# OMODRI_Encoders.net
KiCad netlist of a schematic drawn in Altium Designer
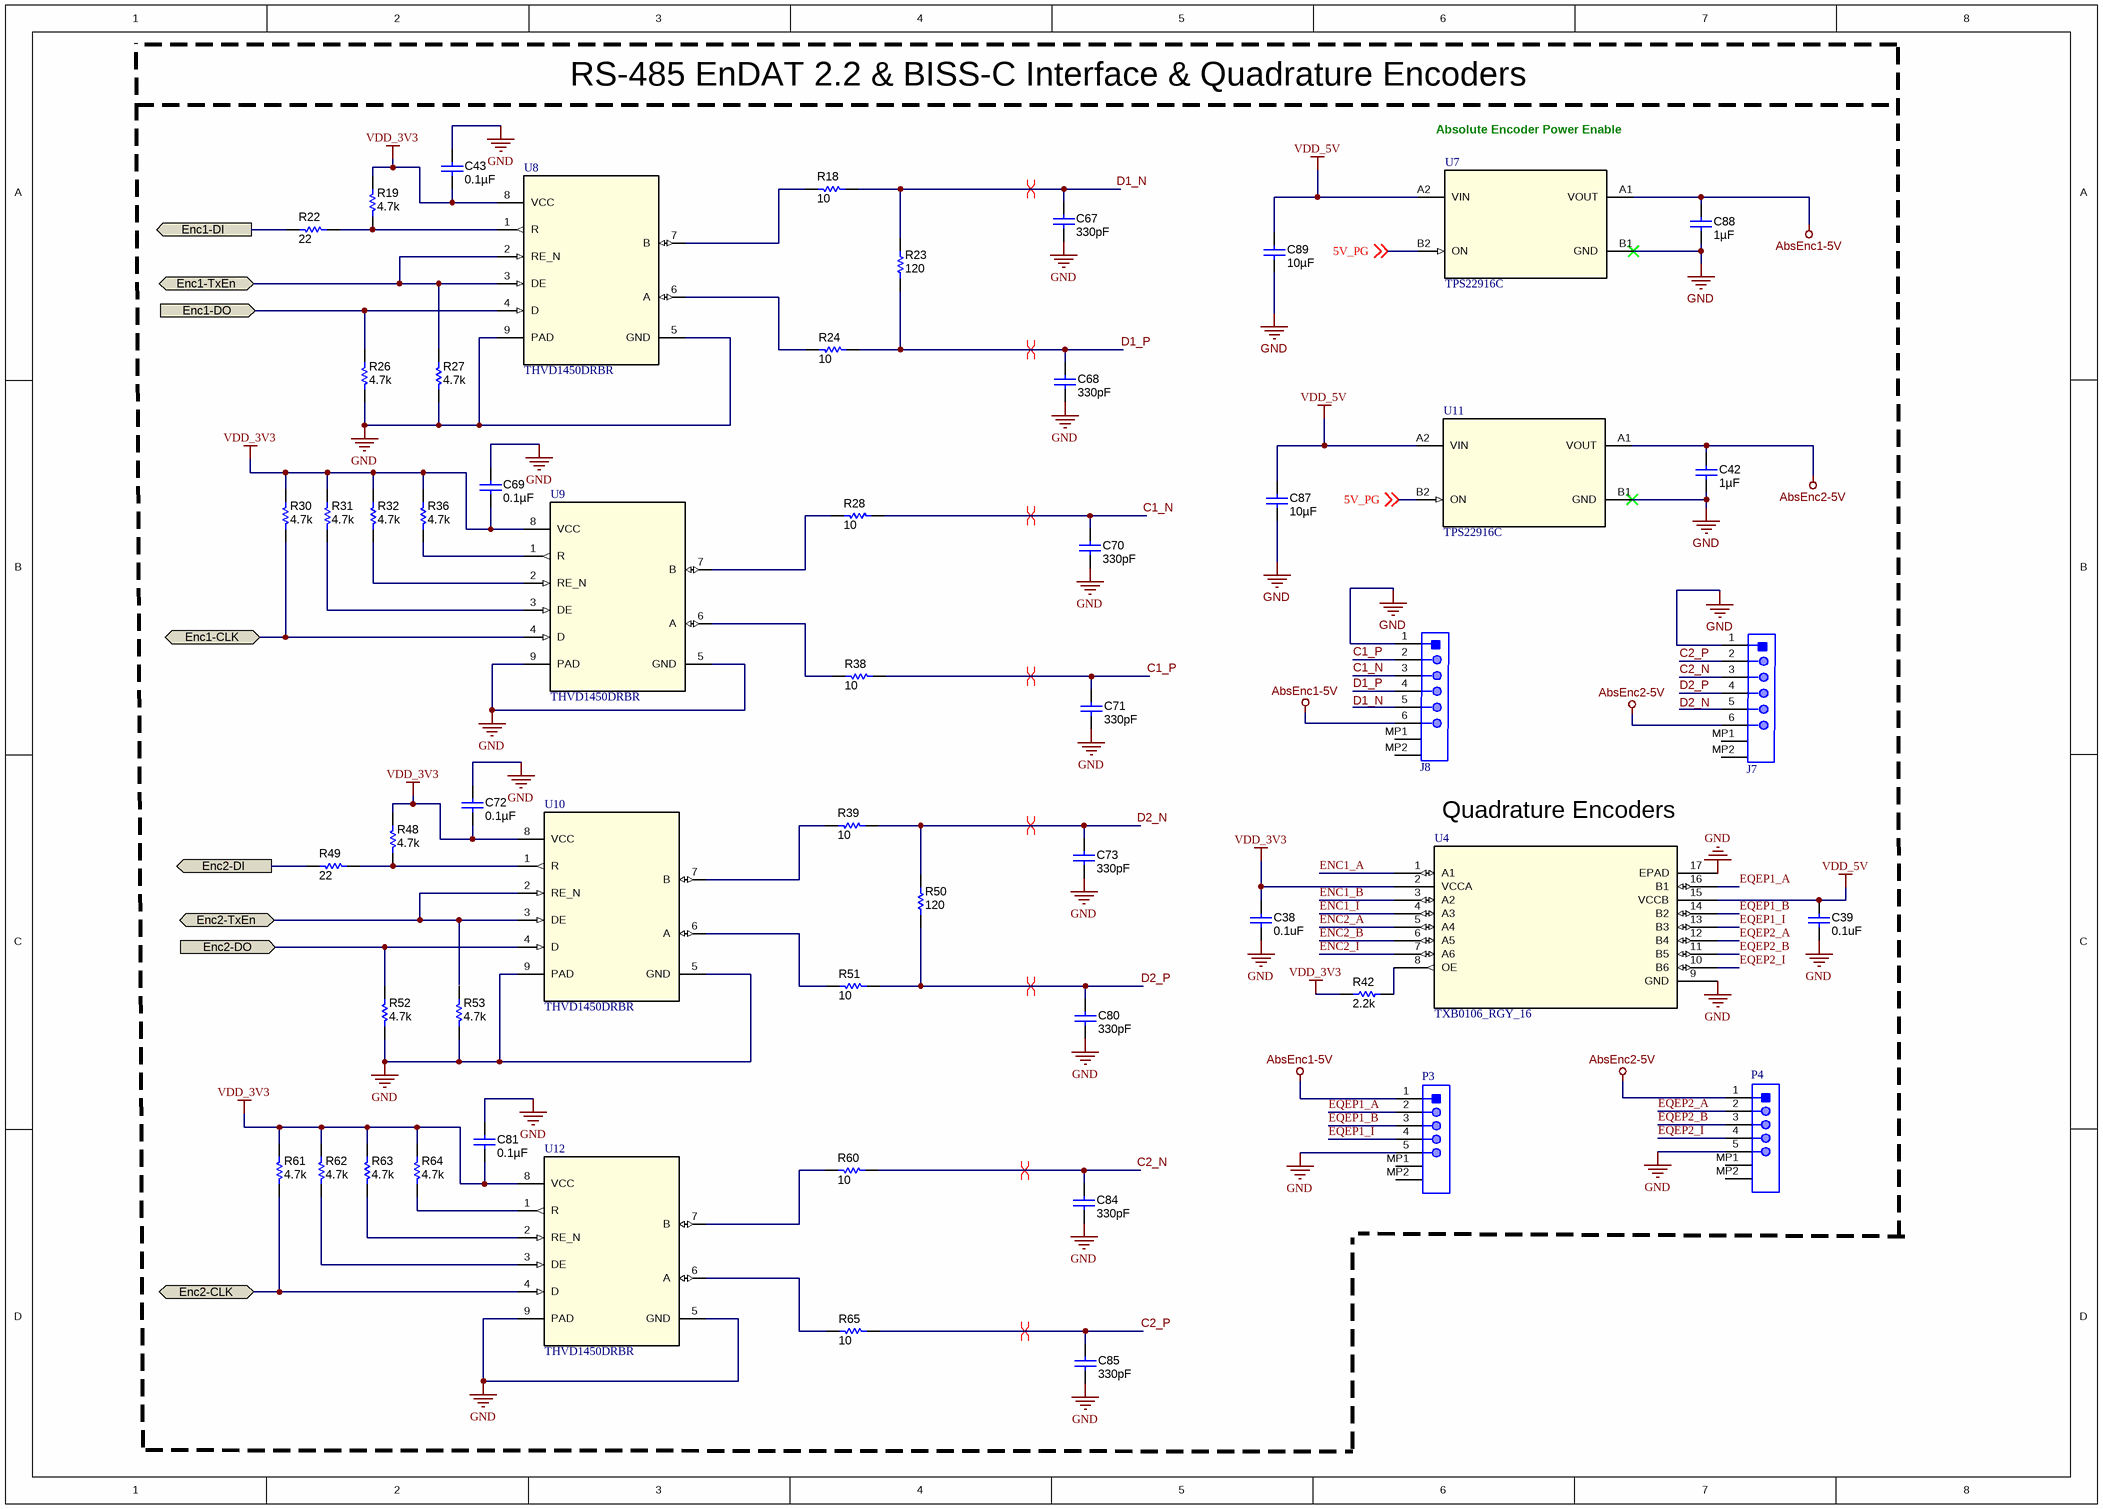
[diagram p0: OMODRI_Encoders.SchDoc]

(export (version "E")
  (design (tool "Eeschema 10.0.6"))
  (components
    (comp (ref "C38")
      (value "CL05B104KP5NNNC")
      (footprint "0402")
      (description "CAP, CERM, 0.1 uF, 10 V, +/- 10%, X7R, 0402")
      (fields
        (field (name "VALUEDISPLAYED") "0.1uF")
        (field (name "MANUFACTURER") "Samsung Electro-Mechanics")
        (field (name "PUBLISHER") "Texas Instruments")
      )
      (libsource (lib "Altium Vault - TI") (part "Capacitor"))
    )
    (comp (ref "C39")
      (value "CL05B104KP5NNNC")
      (footprint "0402")
      (description "CAP, CERM, 0.1 uF, 10 V, +/- 10%, X7R, 0402")
      (fields
        (field (name "VALUEDISPLAYED") "0.1uF")
        (field (name "MANUFACTURER") "Samsung Electro-Mechanics")
        (field (name "PUBLISHER") "Texas Instruments")
      )
      (libsource (lib "Altium Vault - TI") (part "Capacitor"))
    )
    (comp (ref "C42")
      (value "TMK212BJ105KG-T")
      (footprint "0805_HV")
      (description "CAP, CERM, 1 µF, 20 V, +/- 10%, X5R, 0805")
      (fields
        (field (name "VALUEDISPLAYED") "1µF")
        (field (name "MANUFACTURER") "Taiyo Yuden")
        (field (name "PUBLISHER") "Texas Instruments")
      )
      (libsource (lib "Capacitor_Ceramic") (part "TMK212BJ105KG-T"))
    )
    (comp (ref "C43")
      (value "06033D104KAT2A")
      (footprint "0603")
      (description "CAP, CERM, 0.1uF, 25V, +/-10%, X5R, 0603")
      (fields
        (field (name "VALUEDISPLAYED") "0.1µF")
        (field (name "MANUFACTURER") "AVX")
        (field (name "PUBLISHER") "Texas Instruments")
      )
      (libsource (lib "Capacitor_Ceramic") (part "06033D104KAT2A"))
    )
    (comp (ref "C67")
      (value "GRM188R71H331KA01D")
      (footprint "0603")
      (description "CAP, CERM, 330pF, 50V, +/-10%, X7R, 0603")
      (fields
        (field (name "VALUEDISPLAYED") "330pF")
        (field (name "MANUFACTURER") "MuRata")
        (field (name "PUBLISHER") "Texas Instruments")
      )
      (libsource (lib "Capacitor_Ceramic") (part "GRM188R71H331KA01D"))
    )
    (comp (ref "C68")
      (value "GRM188R71H331KA01D")
      (footprint "0603")
      (description "CAP, CERM, 330pF, 50V, +/-10%, X7R, 0603")
      (fields
        (field (name "VALUEDISPLAYED") "330pF")
        (field (name "MANUFACTURER") "MuRata")
        (field (name "PUBLISHER") "Texas Instruments")
      )
      (libsource (lib "Capacitor_Ceramic") (part "GRM188R71H331KA01D"))
    )
    (comp (ref "C69")
      (value "06033D104KAT2A")
      (footprint "0603")
      (description "CAP, CERM, 0.1uF, 25V, +/-10%, X5R, 0603")
      (fields
        (field (name "VALUEDISPLAYED") "0.1µF")
        (field (name "MANUFACTURER") "AVX")
        (field (name "PUBLISHER") "Texas Instruments")
      )
      (libsource (lib "Capacitor_Ceramic") (part "06033D104KAT2A"))
    )
    (comp (ref "C70")
      (value "GRM188R71H331KA01D")
      (footprint "0603")
      (description "CAP, CERM, 330pF, 50V, +/-10%, X7R, 0603")
      (fields
        (field (name "VALUEDISPLAYED") "330pF")
        (field (name "MANUFACTURER") "MuRata")
        (field (name "PUBLISHER") "Texas Instruments")
      )
      (libsource (lib "Capacitor_Ceramic") (part "GRM188R71H331KA01D"))
    )
    (comp (ref "C71")
      (value "GRM188R71H331KA01D")
      (footprint "0603")
      (description "CAP, CERM, 330pF, 50V, +/-10%, X7R, 0603")
      (fields
        (field (name "VALUEDISPLAYED") "330pF")
        (field (name "MANUFACTURER") "MuRata")
        (field (name "PUBLISHER") "Texas Instruments")
      )
      (libsource (lib "Capacitor_Ceramic") (part "GRM188R71H331KA01D"))
    )
    (comp (ref "C72")
      (value "06033D104KAT2A")
      (footprint "0603")
      (description "CAP, CERM, 0.1uF, 25V, +/-10%, X5R, 0603")
      (fields
        (field (name "VALUEDISPLAYED") "0.1µF")
        (field (name "MANUFACTURER") "AVX")
        (field (name "PUBLISHER") "Texas Instruments")
      )
      (libsource (lib "Capacitor_Ceramic") (part "06033D104KAT2A"))
    )
    (comp (ref "C73")
      (value "GRM188R71H331KA01D")
      (footprint "0603")
      (description "CAP, CERM, 330pF, 50V, +/-10%, X7R, 0603")
      (fields
        (field (name "VALUEDISPLAYED") "330pF")
        (field (name "MANUFACTURER") "MuRata")
        (field (name "PUBLISHER") "Texas Instruments")
      )
      (libsource (lib "Capacitor_Ceramic") (part "GRM188R71H331KA01D"))
    )
    (comp (ref "C80")
      (value "GRM188R71H331KA01D")
      (footprint "0603")
      (description "CAP, CERM, 330pF, 50V, +/-10%, X7R, 0603")
      (fields
        (field (name "VALUEDISPLAYED") "330pF")
        (field (name "MANUFACTURER") "MuRata")
        (field (name "PUBLISHER") "Texas Instruments")
      )
      (libsource (lib "Capacitor_Ceramic") (part "GRM188R71H331KA01D"))
    )
    (comp (ref "C81")
      (value "06033D104KAT2A")
      (footprint "0603")
      (description "CAP, CERM, 0.1uF, 25V, +/-10%, X5R, 0603")
      (fields
        (field (name "VALUEDISPLAYED") "0.1µF")
        (field (name "MANUFACTURER") "AVX")
        (field (name "PUBLISHER") "Texas Instruments")
      )
      (libsource (lib "Capacitor_Ceramic") (part "06033D104KAT2A"))
    )
    (comp (ref "C84")
      (value "GRM188R71H331KA01D")
      (footprint "0603")
      (description "CAP, CERM, 330pF, 50V, +/-10%, X7R, 0603")
      (fields
        (field (name "VALUEDISPLAYED") "330pF")
        (field (name "MANUFACTURER") "MuRata")
        (field (name "PUBLISHER") "Texas Instruments")
      )
      (libsource (lib "Capacitor_Ceramic") (part "GRM188R71H331KA01D"))
    )
    (comp (ref "C85")
      (value "GRM188R71H331KA01D")
      (footprint "0603")
      (description "CAP, CERM, 330pF, 50V, +/-10%, X7R, 0603")
      (fields
        (field (name "VALUEDISPLAYED") "330pF")
        (field (name "MANUFACTURER") "MuRata")
        (field (name "PUBLISHER") "Texas Instruments")
      )
      (libsource (lib "Capacitor_Ceramic") (part "GRM188R71H331KA01D"))
    )
    (comp (ref "C87")
      (value "GRM21BR61E106KA73L")
      (footprint "0805_HV")
      (description "CAP, CERM, 10 µF, 25 V,+/- 10%, X5R, 0805")
      (fields
        (field (name "VALUEDISPLAYED") "10µF")
        (field (name "MANUFACTURER") "MuRata")
        (field (name "PUBLISHER") "Texas Instruments")
      )
      (libsource (lib "Capacitor_Ceramic") (part "GRM21BR61E106KA73L"))
    )
    (comp (ref "C88")
      (value "TMK212BJ105KG-T")
      (footprint "0805_HV")
      (description "CAP, CERM, 1 µF, 20 V, +/- 10%, X5R, 0805")
      (fields
        (field (name "VALUEDISPLAYED") "1µF")
        (field (name "MANUFACTURER") "Taiyo Yuden")
        (field (name "PUBLISHER") "Texas Instruments")
      )
      (libsource (lib "Capacitor_Ceramic") (part "TMK212BJ105KG-T"))
    )
    (comp (ref "C89")
      (value "GRM21BR61E106KA73L")
      (footprint "0805_HV")
      (description "CAP, CERM, 10 µF, 25 V,+/- 10%, X5R, 0805")
      (fields
        (field (name "VALUEDISPLAYED") "10µF")
        (field (name "MANUFACTURER") "MuRata")
        (field (name "PUBLISHER") "Texas Instruments")
      )
      (libsource (lib "Capacitor_Ceramic") (part "GRM21BR61E106KA73L"))
    )
    (comp (ref "J7")
      (value "Conn_JST_BM06B-GHS-TBT_LF_SN_N_eec")
      (footprint "JST_BM06B-GHS-TBT_LF_SN_N_0")
      (description "CONN HEADER GH TOP 6POS 1.25MM")
      (fields (field (name "MANUFACTURER") "JST") (field (name "DIGIKEY PART NUMBER") "455-1582-1-ND"))
      (libsource (lib "JST_GH") (part "Conn_JST_BM06B-GHS-TBT_LF_SN_N_eec"))
    )
    (comp (ref "J8")
      (value "Conn_JST_BM06B-GHS-TBT_LF_SN_N_eec")
      (footprint "JST_BM06B-GHS-TBT_LF_SN_N_0")
      (description "CONN HEADER GH TOP 6POS 1.25MM")
      (fields (field (name "MANUFACTURER") "JST") (field (name "DIGIKEY PART NUMBER") "455-1582-1-ND"))
      (libsource (lib "JST_GH") (part "Conn_JST_BM06B-GHS-TBT_LF_SN_N_eec"))
    )
    (comp (ref "P3")
      (value "BM05B-GHS-TBT(LF)(SN)")
      (footprint "JST-BM05B-GHS-TBT_V")
      (fields (field (name "MANUFACTURER") "JST"))
      (libsource (lib "JST_GH") (part "CMP-2000-05958-1"))
    )
    (comp (ref "P4")
      (value "BM05B-GHS-TBT(LF)(SN)")
      (footprint "JST-BM05B-GHS-TBT_V")
      (fields (field (name "MANUFACTURER") "JST"))
      (libsource (lib "JST_GH") (part "CMP-2000-05958-1"))
    )
    (comp (ref "R18")
      (value "10")
      (footprint "0603")
      (description "RES, 10 ohm, 5%, 0.25W, 0603")
      (fields
        (field (name "PARTNUMBER") "CRCW060310R0JNEAHP")
        (field (name "MANUFACTURER") "Vishay-Dale")
        (field (name "PUBLISHER") "Texas Instruments")
      )
      (libsource (lib "Resistor_0603") (part "CRCW060310R0JNEAHP"))
    )
    (comp (ref "R19")
      (value "4.7k")
      (footprint "0603")
      (description "RES, 4.7k ohm, 5%, 0.1W, 0603")
      (fields
        (field (name "PARTNUMBER") "CRCW06034K70JNEA")
        (field (name "MANUFACTURER") "Vishay-Dale")
        (field (name "PUBLISHER") "Texas Instruments")
      )
      (libsource (lib "Resistor_0603") (part "CRCW06034K70JNEA"))
    )
    (comp (ref "R22")
      (value "22")
      (footprint "0603")
      (description "RES, 22 ohm, 5%, 0.1W, 0603")
      (fields
        (field (name "PARTNUMBER") "CRCW060322R0JNEA")
        (field (name "MANUFACTURER") "Vishay-Dale")
        (field (name "PUBLISHER") "Texas Instruments")
      )
      (libsource (lib "Resistor_0603") (part "CRCW060322R0JNEA"))
    )
    (comp (ref "R23")
      (value "CRCW0603120RJNEA")
      (footprint "0603")
      (description "RES, 120, 5%, 0.1 W, 0603")
      (fields
        (field (name "VALUEDISPLAYED") "120")
        (field (name "MANUFACTURER") "Vishay-Dale")
        (field (name "PUBLISHER") "Texas Instruments")
      )
      (libsource (lib "Resistor_0603") (part "CRCW0603120RJNEA"))
    )
    (comp (ref "R24")
      (value "10")
      (footprint "0603")
      (description "RES, 10 ohm, 5%, 0.25W, 0603")
      (fields
        (field (name "PARTNUMBER") "CRCW060310R0JNEAHP")
        (field (name "MANUFACTURER") "Vishay-Dale")
        (field (name "PUBLISHER") "Texas Instruments")
      )
      (libsource (lib "Resistor_0603") (part "CRCW060310R0JNEAHP"))
    )
    (comp (ref "R26")
      (value "4.7k")
      (footprint "0603")
      (description "RES, 4.7k ohm, 5%, 0.1W, 0603")
      (fields
        (field (name "PARTNUMBER") "CRCW06034K70JNEA")
        (field (name "MANUFACTURER") "Vishay-Dale")
        (field (name "PUBLISHER") "Texas Instruments")
      )
      (libsource (lib "Resistor_0603") (part "CRCW06034K70JNEA"))
    )
    (comp (ref "R27")
      (value "4.7k")
      (footprint "0603")
      (description "RES, 4.7k ohm, 5%, 0.1W, 0603")
      (fields
        (field (name "PARTNUMBER") "CRCW06034K70JNEA")
        (field (name "MANUFACTURER") "Vishay-Dale")
        (field (name "PUBLISHER") "Texas Instruments")
      )
      (libsource (lib "Resistor_0603") (part "CRCW06034K70JNEA"))
    )
    (comp (ref "R28")
      (value "10")
      (footprint "0603")
      (description "RES, 10 ohm, 5%, 0.25W, 0603")
      (fields
        (field (name "PARTNUMBER") "CRCW060310R0JNEAHP")
        (field (name "MANUFACTURER") "Vishay-Dale")
        (field (name "PUBLISHER") "Texas Instruments")
      )
      (libsource (lib "Resistor_0603") (part "CRCW060310R0JNEAHP"))
    )
    (comp (ref "R30")
      (value "4.7k")
      (footprint "0603")
      (description "RES, 4.7k ohm, 5%, 0.1W, 0603")
      (fields
        (field (name "PARTNUMBER") "CRCW06034K70JNEA")
        (field (name "MANUFACTURER") "Vishay-Dale")
        (field (name "PUBLISHER") "Texas Instruments")
      )
      (libsource (lib "Resistor_0603") (part "CRCW06034K70JNEA"))
    )
    (comp (ref "R31")
      (value "4.7k")
      (footprint "0603")
      (description "RES, 4.7k ohm, 5%, 0.1W, 0603")
      (fields
        (field (name "PARTNUMBER") "CRCW06034K70JNEA")
        (field (name "MANUFACTURER") "Vishay-Dale")
        (field (name "PUBLISHER") "Texas Instruments")
      )
      (libsource (lib "Resistor_0603") (part "CRCW06034K70JNEA"))
    )
    (comp (ref "R32")
      (value "4.7k")
      (footprint "0603")
      (description "RES, 4.7k ohm, 5%, 0.1W, 0603")
      (fields
        (field (name "PARTNUMBER") "CRCW06034K70JNEA")
        (field (name "MANUFACTURER") "Vishay-Dale")
        (field (name "PUBLISHER") "Texas Instruments")
      )
      (libsource (lib "Resistor_0603") (part "CRCW06034K70JNEA"))
    )
    (comp (ref "R36")
      (value "4.7k")
      (footprint "0603")
      (description "RES, 4.7k ohm, 5%, 0.1W, 0603")
      (fields
        (field (name "PARTNUMBER") "CRCW06034K70JNEA")
        (field (name "MANUFACTURER") "Vishay-Dale")
        (field (name "PUBLISHER") "Texas Instruments")
      )
      (libsource (lib "Resistor_0603") (part "CRCW06034K70JNEA"))
    )
    (comp (ref "R38")
      (value "10")
      (footprint "0603")
      (description "RES, 10 ohm, 5%, 0.25W, 0603")
      (fields
        (field (name "PARTNUMBER") "CRCW060310R0JNEAHP")
        (field (name "MANUFACTURER") "Vishay-Dale")
        (field (name "PUBLISHER") "Texas Instruments")
      )
      (libsource (lib "Resistor_0603") (part "CRCW060310R0JNEAHP"))
    )
    (comp (ref "R39")
      (value "10")
      (footprint "0603")
      (description "RES, 10 ohm, 5%, 0.25W, 0603")
      (fields
        (field (name "PARTNUMBER") "CRCW060310R0JNEAHP")
        (field (name "MANUFACTURER") "Vishay-Dale")
        (field (name "PUBLISHER") "Texas Instruments")
      )
      (libsource (lib "Resistor_0603") (part "CRCW060310R0JNEAHP"))
    )
    (comp (ref "R42")
      (value "CRCW02012K20JNED")
      (footprint "0201")
      (description "RES, 2.2 k, 5%, 0.05 W, 0201")
      (fields (field (name "MANUFACTURER") "Vishay-Dale") (field (name "VALUEDISPLAYED") "2.2k"))
      (libsource (lib "Altium Vault - TI") (part "Resistor"))
    )
    (comp (ref "R48")
      (value "4.7k")
      (footprint "0603")
      (description "RES, 4.7k ohm, 5%, 0.1W, 0603")
      (fields
        (field (name "PARTNUMBER") "CRCW06034K70JNEA")
        (field (name "MANUFACTURER") "Vishay-Dale")
        (field (name "PUBLISHER") "Texas Instruments")
      )
      (libsource (lib "Resistor_0603") (part "CRCW06034K70JNEA"))
    )
    (comp (ref "R49")
      (value "22")
      (footprint "0603")
      (description "RES, 22 ohm, 5%, 0.1W, 0603")
      (fields
        (field (name "PARTNUMBER") "CRCW060322R0JNEA")
        (field (name "MANUFACTURER") "Vishay-Dale")
        (field (name "PUBLISHER") "Texas Instruments")
      )
      (libsource (lib "Resistor_0603") (part "CRCW060322R0JNEA"))
    )
    (comp (ref "R50")
      (value "CRCW0603120RJNEA")
      (footprint "0603")
      (description "RES, 120, 5%, 0.1 W, 0603")
      (fields
        (field (name "VALUEDISPLAYED") "120")
        (field (name "MANUFACTURER") "Vishay-Dale")
        (field (name "PUBLISHER") "Texas Instruments")
      )
      (libsource (lib "Resistor_0603") (part "CRCW0603120RJNEA"))
    )
    (comp (ref "R51")
      (value "10")
      (footprint "0603")
      (description "RES, 10 ohm, 5%, 0.25W, 0603")
      (fields
        (field (name "PARTNUMBER") "CRCW060310R0JNEAHP")
        (field (name "MANUFACTURER") "Vishay-Dale")
        (field (name "PUBLISHER") "Texas Instruments")
      )
      (libsource (lib "Resistor_0603") (part "CRCW060310R0JNEAHP"))
    )
    (comp (ref "R52")
      (value "4.7k")
      (footprint "0603")
      (description "RES, 4.7k ohm, 5%, 0.1W, 0603")
      (fields
        (field (name "PARTNUMBER") "CRCW06034K70JNEA")
        (field (name "MANUFACTURER") "Vishay-Dale")
        (field (name "PUBLISHER") "Texas Instruments")
      )
      (libsource (lib "Resistor_0603") (part "CRCW06034K70JNEA"))
    )
    (comp (ref "R53")
      (value "4.7k")
      (footprint "0603")
      (description "RES, 4.7k ohm, 5%, 0.1W, 0603")
      (fields
        (field (name "PARTNUMBER") "CRCW06034K70JNEA")
        (field (name "MANUFACTURER") "Vishay-Dale")
        (field (name "PUBLISHER") "Texas Instruments")
      )
      (libsource (lib "Resistor_0603") (part "CRCW06034K70JNEA"))
    )
    (comp (ref "R60")
      (value "10")
      (footprint "0603")
      (description "RES, 10 ohm, 5%, 0.25W, 0603")
      (fields
        (field (name "PARTNUMBER") "CRCW060310R0JNEAHP")
        (field (name "MANUFACTURER") "Vishay-Dale")
        (field (name "PUBLISHER") "Texas Instruments")
      )
      (libsource (lib "Resistor_0603") (part "CRCW060310R0JNEAHP"))
    )
    (comp (ref "R61")
      (value "4.7k")
      (footprint "0603")
      (description "RES, 4.7k ohm, 5%, 0.1W, 0603")
      (fields
        (field (name "PARTNUMBER") "CRCW06034K70JNEA")
        (field (name "MANUFACTURER") "Vishay-Dale")
        (field (name "PUBLISHER") "Texas Instruments")
      )
      (libsource (lib "Resistor_0603") (part "CRCW06034K70JNEA"))
    )
    (comp (ref "R62")
      (value "4.7k")
      (footprint "0603")
      (description "RES, 4.7k ohm, 5%, 0.1W, 0603")
      (fields
        (field (name "PARTNUMBER") "CRCW06034K70JNEA")
        (field (name "MANUFACTURER") "Vishay-Dale")
        (field (name "PUBLISHER") "Texas Instruments")
      )
      (libsource (lib "Resistor_0603") (part "CRCW06034K70JNEA"))
    )
    (comp (ref "R63")
      (value "4.7k")
      (footprint "0603")
      (description "RES, 4.7k ohm, 5%, 0.1W, 0603")
      (fields
        (field (name "PARTNUMBER") "CRCW06034K70JNEA")
        (field (name "MANUFACTURER") "Vishay-Dale")
        (field (name "PUBLISHER") "Texas Instruments")
      )
      (libsource (lib "Resistor_0603") (part "CRCW06034K70JNEA"))
    )
    (comp (ref "R64")
      (value "4.7k")
      (footprint "0603")
      (description "RES, 4.7k ohm, 5%, 0.1W, 0603")
      (fields
        (field (name "PARTNUMBER") "CRCW06034K70JNEA")
        (field (name "MANUFACTURER") "Vishay-Dale")
        (field (name "PUBLISHER") "Texas Instruments")
      )
      (libsource (lib "Resistor_0603") (part "CRCW06034K70JNEA"))
    )
    (comp (ref "R65")
      (value "10")
      (footprint "0603")
      (description "RES, 10 ohm, 5%, 0.25W, 0603")
      (fields
        (field (name "PARTNUMBER") "CRCW060310R0JNEAHP")
        (field (name "MANUFACTURER") "Vishay-Dale")
        (field (name "PUBLISHER") "Texas Instruments")
      )
      (libsource (lib "Resistor_0603") (part "CRCW060310R0JNEAHP"))
    )
    (comp (ref "U4")
      (value "TXB0106_RGY_16")
      (footprint "RGY16_2P55X2P05")
      (fields
        (field (name "MANUFACTURER_PART_NUMBER") "txb0106_rgy_16")
        (field (name "GENERIC_PART_NUMBER") "TXB0106")
        (field (name "MANUFACTURER") "Texas Instruments")
      )
      (libsource (lib "Texas_Instruments") (part "TXB0106_RGY_16"))
    )
    (comp (ref "U7")
      (value "TPS22916C")
      (footprint "YFP0004ABAB")
      (description "TPS22916CY Single-Channel Ultra-Low Leakage Load Switch 2A 60 mO 1V to 5.5V 4-Pin DSBGA T/R")
      (fields
        (field (name "MANUFACTURER") "Texas Instruments")
        (field (name "MANUFACTURER PART NUMBER") "TPS22916CYFPR")
      )
      (libsource (lib "Texas_Instruments") (part "TPS22916C"))
    )
    (comp (ref "U8")
      (value "THVD1450DRBR")
      (footprint "DRB0008F")
      (fields (field (name "MANUFACTURER") "Texas Instruments"))
      (libsource (lib "Texas_Instruments") (part "THVD1450DRBR"))
    )
    (comp (ref "U9")
      (value "THVD1450DRBR")
      (footprint "DRB0008F")
      (fields (field (name "MANUFACTURER") "Texas Instruments"))
      (libsource (lib "Texas_Instruments") (part "THVD1450DRBR"))
    )
    (comp (ref "U10")
      (value "THVD1450DRBR")
      (footprint "DRB0008F")
      (fields (field (name "MANUFACTURER") "Texas Instruments"))
      (libsource (lib "Texas_Instruments") (part "THVD1450DRBR"))
    )
    (comp (ref "U11")
      (value "TPS22916C")
      (footprint "YFP0004ABAB")
      (description "TPS22916CY Single-Channel Ultra-Low Leakage Load Switch 2A 60 mO 1V to 5.5V 4-Pin DSBGA T/R")
      (fields
        (field (name "MANUFACTURER") "Texas Instruments")
        (field (name "MANUFACTURER PART NUMBER") "TPS22916CYFPR")
      )
      (libsource (lib "Texas_Instruments") (part "TPS22916C"))
    )
    (comp (ref "U12")
      (value "THVD1450DRBR")
      (footprint "DRB0008F")
      (fields (field (name "MANUFACTURER") "Texas Instruments"))
      (libsource (lib "Texas_Instruments") (part "THVD1450DRBR"))
    )
  )
  (nets
    (net (code "1") (name "/C1_N") (class "Default")
      (node (ref "C70") (pin "2") (pinfunction "2_2") (pintype "passive"))
      (node (ref "J8") (pin "3") (pinfunction "3_3") (pintype "passive"))
      (node (ref "R28") (pin "1") (pinfunction "1_1") (pintype "passive"))
    )
    (net (code "2") (name "/C1_P") (class "Default")
      (node (ref "C71") (pin "1") (pinfunction "1_1") (pintype "passive"))
      (node (ref "J8") (pin "2") (pinfunction "2_2") (pintype "passive"))
      (node (ref "R38") (pin "1") (pinfunction "1_1") (pintype "passive"))
    )
    (net (code "3") (name "/C2_N") (class "Default")
      (node (ref "C84") (pin "2") (pinfunction "2_2") (pintype "passive"))
      (node (ref "J7") (pin "3") (pinfunction "3_3") (pintype "passive"))
      (node (ref "R60") (pin "1") (pinfunction "1_1") (pintype "passive"))
    )
    (net (code "4") (name "/C2_P") (class "Default")
      (node (ref "C85") (pin "1") (pinfunction "1_1") (pintype "passive"))
      (node (ref "J7") (pin "2") (pinfunction "2_2") (pintype "passive"))
      (node (ref "R65") (pin "1") (pinfunction "1_1") (pintype "passive"))
    )
    (net (code "5") (name "/D1_N") (class "Default")
      (node (ref "C67") (pin "2") (pinfunction "2_2") (pintype "passive"))
      (node (ref "R18") (pin "1") (pinfunction "1_1") (pintype "passive"))
      (node (ref "R23") (pin "2") (pinfunction "2_2") (pintype "passive"))
    )
    (net (code "6") (name "/D1_P") (class "Default")
      (node (ref "C68") (pin "1") (pinfunction "1_1") (pintype "passive"))
      (node (ref "J8") (pin "4") (pinfunction "4_4") (pintype "passive"))
      (node (ref "R23") (pin "1") (pinfunction "1_1") (pintype "passive"))
      (node (ref "R24") (pin "1") (pinfunction "1_1") (pintype "passive"))
    )
    (net (code "7") (name "/D2_N") (class "Default")
      (node (ref "C73") (pin "2") (pinfunction "2_2") (pintype "passive"))
      (node (ref "R39") (pin "1") (pinfunction "1_1") (pintype "passive"))
      (node (ref "R50") (pin "2") (pinfunction "2_2") (pintype "passive"))
    )
    (net (code "8") (name "/D2_P") (class "Default")
      (node (ref "C80") (pin "1") (pinfunction "1_1") (pintype "passive"))
      (node (ref "J7") (pin "4") (pinfunction "4_4") (pintype "passive"))
      (node (ref "R50") (pin "1") (pinfunction "1_1") (pintype "passive"))
      (node (ref "R51") (pin "1") (pinfunction "1_1") (pintype "passive"))
    )
    (net (code "9") (name "/ENC1_A") (class "Default")
      (node (ref "U4") (pin "1") (pinfunction "A1_1") (pintype "bidirectional"))
    )
    (net (code "10") (name "/ENC1_B") (class "Default")
      (node (ref "U4") (pin "3") (pinfunction "A2_3") (pintype "bidirectional"))
    )
    (net (code "11") (name "/ENC1_I") (class "Default")
      (node (ref "U4") (pin "4") (pinfunction "A3_4") (pintype "bidirectional"))
    )
    (net (code "12") (name "/ENC2_A") (class "Default")
      (node (ref "U4") (pin "5") (pinfunction "A4_5") (pintype "bidirectional"))
    )
    (net (code "13") (name "/ENC2_B") (class "Default")
      (node (ref "U4") (pin "6") (pinfunction "A5_6") (pintype "bidirectional"))
    )
    (net (code "14") (name "/ENC2_I") (class "Default")
      (node (ref "U4") (pin "7") (pinfunction "A6_7") (pintype "bidirectional"))
    )
    (net (code "15") (name "/EQEP1_A") (class "Default")
      (node (ref "P3") (pin "2") (pinfunction "2_2") (pintype "passive"))
      (node (ref "U4") (pin "16") (pinfunction "B1_16") (pintype "bidirectional"))
    )
    (net (code "16") (name "/EQEP1_B") (class "Default")
      (node (ref "P3") (pin "3") (pinfunction "3_3") (pintype "passive"))
      (node (ref "U4") (pin "14") (pinfunction "B2_14") (pintype "bidirectional"))
    )
    (net (code "17") (name "/EQEP1_I") (class "Default")
      (node (ref "P3") (pin "4") (pinfunction "4_4") (pintype "passive"))
      (node (ref "U4") (pin "13") (pinfunction "B3_13") (pintype "bidirectional"))
    )
    (net (code "18") (name "/EQEP2_A") (class "Default")
      (node (ref "P4") (pin "2") (pinfunction "2_2") (pintype "passive"))
      (node (ref "U4") (pin "12") (pinfunction "B4_12") (pintype "bidirectional"))
    )
    (net (code "19") (name "/EQEP2_B") (class "Default")
      (node (ref "P4") (pin "3") (pinfunction "3_3") (pintype "passive"))
      (node (ref "U4") (pin "11") (pinfunction "B5_11") (pintype "bidirectional"))
    )
    (net (code "20") (name "/EQEP2_I") (class "Default")
      (node (ref "P4") (pin "4") (pinfunction "4_4") (pintype "passive"))
      (node (ref "U4") (pin "10") (pinfunction "B6_10") (pintype "bidirectional"))
    )
    (net (code "21") (name "/Enc1-CLK") (class "Default")
      (node (ref "R30") (pin "2") (pinfunction "2_2") (pintype "passive"))
      (node (ref "U9") (pin "4") (pinfunction "D_4") (pintype "input"))
    )
    (net (code "22") (name "/Enc1-DI") (class "Default")
      (node (ref "R22") (pin "2") (pinfunction "2_2") (pintype "passive"))
    )
    (net (code "23") (name "/Enc1-DO") (class "Default")
      (node (ref "R26") (pin "1") (pinfunction "1_1") (pintype "passive"))
      (node (ref "U8") (pin "4") (pinfunction "D_4") (pintype "input"))
    )
    (net (code "24") (name "/Enc1-TxEn") (class "Default")
      (node (ref "U8") (pin "2") (pinfunction "RE_N_2") (pintype "input"))
      (node (ref "U8") (pin "3") (pinfunction "DE_3") (pintype "input"))
    )
    (net (code "25") (name "/Enc2-CLK") (class "Default")
      (node (ref "R61") (pin "2") (pinfunction "2_2") (pintype "passive"))
      (node (ref "U12") (pin "4") (pinfunction "D_4") (pintype "input"))
    )
    (net (code "26") (name "/Enc2-DI") (class "Default")
      (node (ref "R49") (pin "2") (pinfunction "2_2") (pintype "passive"))
    )
    (net (code "27") (name "/Enc2-DO") (class "Default")
      (node (ref "R52") (pin "1") (pinfunction "1_1") (pintype "passive"))
      (node (ref "U10") (pin "4") (pinfunction "D_4") (pintype "input"))
    )
    (net (code "28") (name "/Enc2-TxEn") (class "Default")
      (node (ref "U10") (pin "2") (pinfunction "RE_N_2") (pintype "input"))
      (node (ref "U10") (pin "3") (pinfunction "DE_3") (pintype "input"))
    )
    (net (code "29") (name "5V_PG") (class "Default")
      (node (ref "U11") (pin "B2") (pinfunction "ON_B2") (pintype "input"))
      (node (ref "U7") (pin "B2") (pinfunction "ON_B2") (pintype "input"))
    )
    (net (code "30") (name "AbsEnc1-5V") (class "Default")
      (node (ref "C88") (pin "1") (pinfunction "1_1") (pintype "passive"))
      (node (ref "J8") (pin "6") (pinfunction "6_6") (pintype "passive"))
      (node (ref "P3") (pin "1") (pinfunction "1_1") (pintype "passive"))
      (node (ref "U7") (pin "A1") (pinfunction "VOUT_A1") (pintype "power_in"))
    )
    (net (code "31") (name "AbsEnc2-5V") (class "Default")
      (node (ref "C42") (pin "1") (pinfunction "1_1") (pintype "passive"))
      (node (ref "J7") (pin "6") (pinfunction "6_6") (pintype "passive"))
      (node (ref "P4") (pin "1") (pinfunction "1_1") (pintype "passive"))
      (node (ref "U11") (pin "A1") (pinfunction "VOUT_A1") (pintype "power_in"))
    )
    (net (code "32") (name "GND") (class "Default")
      (node (ref "C38") (pin "2") (pinfunction "2_2") (pintype "passive"))
      (node (ref "C39") (pin "2") (pinfunction "2_2") (pintype "passive"))
      (node (ref "C42") (pin "2") (pinfunction "2_2") (pintype "passive"))
      (node (ref "C43") (pin "2") (pinfunction "2_2") (pintype "passive"))
      (node (ref "C67") (pin "1") (pinfunction "1_1") (pintype "passive"))
      (node (ref "C68") (pin "2") (pinfunction "2_2") (pintype "passive"))
      (node (ref "C69") (pin "2") (pinfunction "2_2") (pintype "passive"))
      (node (ref "C70") (pin "1") (pinfunction "1_1") (pintype "passive"))
      (node (ref "C71") (pin "2") (pinfunction "2_2") (pintype "passive"))
      (node (ref "C72") (pin "2") (pinfunction "2_2") (pintype "passive"))
      (node (ref "C73") (pin "1") (pinfunction "1_1") (pintype "passive"))
      (node (ref "C80") (pin "2") (pinfunction "2_2") (pintype "passive"))
      (node (ref "C81") (pin "2") (pinfunction "2_2") (pintype "passive"))
      (node (ref "C84") (pin "1") (pinfunction "1_1") (pintype "passive"))
      (node (ref "C85") (pin "2") (pinfunction "2_2") (pintype "passive"))
      (node (ref "C87") (pin "2") (pinfunction "2_2") (pintype "passive"))
      (node (ref "C88") (pin "2") (pinfunction "2_2") (pintype "passive"))
      (node (ref "C89") (pin "2") (pinfunction "2_2") (pintype "passive"))
      (node (ref "J7") (pin "1") (pinfunction "1_1") (pintype "passive"))
      (node (ref "J8") (pin "1") (pinfunction "1_1") (pintype "passive"))
      (node (ref "P3") (pin "5") (pinfunction "5_5") (pintype "passive"))
      (node (ref "P4") (pin "5") (pinfunction "5_5") (pintype "passive"))
      (node (ref "R26") (pin "2") (pinfunction "2_2") (pintype "passive"))
      (node (ref "R27") (pin "2") (pinfunction "2_2") (pintype "passive"))
      (node (ref "R52") (pin "2") (pinfunction "2_2") (pintype "passive"))
      (node (ref "R53") (pin "2") (pinfunction "2_2") (pintype "passive"))
      (node (ref "U10") (pin "5") (pinfunction "GND_5") (pintype "power_in"))
      (node (ref "U10") (pin "9") (pinfunction "PAD_9") (pintype "passive"))
      (node (ref "U11") (pin "B1") (pinfunction "GND_B1") (pintype "power_in"))
      (node (ref "U12") (pin "5") (pinfunction "GND_5") (pintype "power_in"))
      (node (ref "U12") (pin "9") (pinfunction "PAD_9") (pintype "passive"))
      (node (ref "U4") (pin "17") (pinfunction "EPAD_17") (pintype "passive"))
      (node (ref "U4") (pin "9") (pinfunction "GND_9") (pintype "power_in"))
      (node (ref "U7") (pin "B1") (pinfunction "GND_B1") (pintype "power_in"))
      (node (ref "U8") (pin "5") (pinfunction "GND_5") (pintype "power_in"))
      (node (ref "U8") (pin "9") (pinfunction "PAD_9") (pintype "passive"))
      (node (ref "U9") (pin "5") (pinfunction "GND_5") (pintype "power_in"))
      (node (ref "U9") (pin "9") (pinfunction "PAD_9") (pintype "passive"))
    )
    (net (code "33") (name "Net-(U4-OE)") (class "Default")
      (node (ref "R42") (pin "2") (pinfunction "2_2") (pintype "passive"))
      (node (ref "U4") (pin "8") (pinfunction "OE_8") (pintype "output"))
    )
    (net (code "34") (name "Net-(U8-A)") (class "Default")
      (node (ref "R24") (pin "2") (pinfunction "2_2") (pintype "passive"))
      (node (ref "U8") (pin "6") (pinfunction "A_6") (pintype "bidirectional"))
    )
    (net (code "35") (name "Net-(U8-B)") (class "Default")
      (node (ref "R18") (pin "2") (pinfunction "2_2") (pintype "passive"))
      (node (ref "U8") (pin "7") (pinfunction "B_7") (pintype "bidirectional"))
    )
    (net (code "36") (name "Net-(U8-R)") (class "Default")
      (node (ref "R19") (pin "1") (pinfunction "1_1") (pintype "passive"))
      (node (ref "R22") (pin "1") (pinfunction "1_1") (pintype "passive"))
      (node (ref "U8") (pin "1") (pinfunction "R_1") (pintype "output"))
    )
    (net (code "37") (name "Net-(U9-A)") (class "Default")
      (node (ref "R38") (pin "2") (pinfunction "2_2") (pintype "passive"))
      (node (ref "U9") (pin "6") (pinfunction "A_6") (pintype "bidirectional"))
    )
    (net (code "38") (name "Net-(U9-B)") (class "Default")
      (node (ref "R28") (pin "2") (pinfunction "2_2") (pintype "passive"))
      (node (ref "U9") (pin "7") (pinfunction "B_7") (pintype "bidirectional"))
    )
    (net (code "39") (name "Net-(U9-DE)") (class "Default")
      (node (ref "R31") (pin "2") (pinfunction "2_2") (pintype "passive"))
      (node (ref "U9") (pin "3") (pinfunction "DE_3") (pintype "input"))
    )
    (net (code "40") (name "Net-(U9-R)") (class "Default")
      (node (ref "R36") (pin "2") (pinfunction "2_2") (pintype "passive"))
      (node (ref "U9") (pin "1") (pinfunction "R_1") (pintype "output"))
    )
    (net (code "41") (name "Net-(U9-RE_N)") (class "Default")
      (node (ref "R32") (pin "2") (pinfunction "2_2") (pintype "passive"))
      (node (ref "U9") (pin "2") (pinfunction "RE_N_2") (pintype "input"))
    )
    (net (code "42") (name "Net-(U10-A)") (class "Default")
      (node (ref "R51") (pin "2") (pinfunction "2_2") (pintype "passive"))
      (node (ref "U10") (pin "6") (pinfunction "A_6") (pintype "bidirectional"))
    )
    (net (code "43") (name "Net-(U10-B)") (class "Default")
      (node (ref "R39") (pin "2") (pinfunction "2_2") (pintype "passive"))
      (node (ref "U10") (pin "7") (pinfunction "B_7") (pintype "bidirectional"))
    )
    (net (code "44") (name "Net-(U10-R)") (class "Default")
      (node (ref "R48") (pin "1") (pinfunction "1_1") (pintype "passive"))
      (node (ref "R49") (pin "1") (pinfunction "1_1") (pintype "passive"))
      (node (ref "U10") (pin "1") (pinfunction "R_1") (pintype "output"))
    )
    (net (code "45") (name "Net-(U12-A)") (class "Default")
      (node (ref "R65") (pin "2") (pinfunction "2_2") (pintype "passive"))
      (node (ref "U12") (pin "6") (pinfunction "A_6") (pintype "bidirectional"))
    )
    (net (code "46") (name "Net-(U12-B)") (class "Default")
      (node (ref "R60") (pin "2") (pinfunction "2_2") (pintype "passive"))
      (node (ref "U12") (pin "7") (pinfunction "B_7") (pintype "bidirectional"))
    )
    (net (code "47") (name "Net-(U12-DE)") (class "Default")
      (node (ref "R62") (pin "2") (pinfunction "2_2") (pintype "passive"))
      (node (ref "U12") (pin "3") (pinfunction "DE_3") (pintype "input"))
    )
    (net (code "48") (name "Net-(U12-R)") (class "Default")
      (node (ref "R64") (pin "2") (pinfunction "2_2") (pintype "passive"))
      (node (ref "U12") (pin "1") (pinfunction "R_1") (pintype "output"))
    )
    (net (code "49") (name "Net-(U12-RE_N)") (class "Default")
      (node (ref "R63") (pin "2") (pinfunction "2_2") (pintype "passive"))
      (node (ref "U12") (pin "2") (pinfunction "RE_N_2") (pintype "input"))
    )
    (net (code "50") (name "VDD_3V3") (class "Default")
      (node (ref "C38") (pin "1") (pinfunction "1_1") (pintype "passive"))
      (node (ref "C43") (pin "1") (pinfunction "1_1") (pintype "passive"))
      (node (ref "C69") (pin "1") (pinfunction "1_1") (pintype "passive"))
      (node (ref "C72") (pin "1") (pinfunction "1_1") (pintype "passive"))
      (node (ref "C81") (pin "1") (pinfunction "1_1") (pintype "passive"))
      (node (ref "R19") (pin "2") (pinfunction "2_2") (pintype "passive"))
      (node (ref "R30") (pin "1") (pinfunction "1_1") (pintype "passive"))
      (node (ref "R31") (pin "1") (pinfunction "1_1") (pintype "passive"))
      (node (ref "R32") (pin "1") (pinfunction "1_1") (pintype "passive"))
      (node (ref "R36") (pin "1") (pinfunction "1_1") (pintype "passive"))
      (node (ref "R42") (pin "1") (pinfunction "1_1") (pintype "passive"))
      (node (ref "R48") (pin "2") (pinfunction "2_2") (pintype "passive"))
      (node (ref "R61") (pin "1") (pinfunction "1_1") (pintype "passive"))
      (node (ref "R62") (pin "1") (pinfunction "1_1") (pintype "passive"))
      (node (ref "R63") (pin "1") (pinfunction "1_1") (pintype "passive"))
      (node (ref "R64") (pin "1") (pinfunction "1_1") (pintype "passive"))
      (node (ref "U10") (pin "8") (pinfunction "VCC_8") (pintype "power_in"))
      (node (ref "U12") (pin "8") (pinfunction "VCC_8") (pintype "power_in"))
      (node (ref "U4") (pin "2") (pinfunction "VCCA_2") (pintype "power_in"))
      (node (ref "U8") (pin "8") (pinfunction "VCC_8") (pintype "power_in"))
      (node (ref "U9") (pin "8") (pinfunction "VCC_8") (pintype "power_in"))
    )
    (net (code "51") (name "VDD_5V") (class "Default")
      (node (ref "C39") (pin "1") (pinfunction "1_1") (pintype "passive"))
      (node (ref "C87") (pin "1") (pinfunction "1_1") (pintype "passive"))
      (node (ref "C89") (pin "1") (pinfunction "1_1") (pintype "passive"))
      (node (ref "U11") (pin "A2") (pinfunction "VIN_A2") (pintype "power_in"))
      (node (ref "U4") (pin "15") (pinfunction "VCCB_15") (pintype "power_in"))
      (node (ref "U7") (pin "A2") (pinfunction "VIN_A2") (pintype "power_in"))
    )
    (net (code "52") (name "unconnected-(J7-Pad5)") (class "Default")
      (node (ref "J7") (pin "5") (pinfunction "5_5") (pintype "passive"))
    )
    (net (code "53") (name "unconnected-(J7-PadMP1)") (class "Default")
      (node (ref "J7") (pin "MP1") (pinfunction "MP1_MP1") (pintype "passive"))
    )
    (net (code "54") (name "unconnected-(J7-PadMP2)") (class "Default")
      (node (ref "J7") (pin "MP2") (pinfunction "MP2_MP2") (pintype "passive"))
    )
    (net (code "55") (name "unconnected-(J8-Pad5)") (class "Default")
      (node (ref "J8") (pin "5") (pinfunction "5_5") (pintype "passive"))
    )
    (net (code "56") (name "unconnected-(J8-PadMP1)") (class "Default")
      (node (ref "J8") (pin "MP1") (pinfunction "MP1_MP1") (pintype "passive"))
    )
    (net (code "57") (name "unconnected-(J8-PadMP2)") (class "Default")
      (node (ref "J8") (pin "MP2") (pinfunction "MP2_MP2") (pintype "passive"))
    )
    (net (code "58") (name "unconnected-(P3-PadMP1)") (class "Default")
      (node (ref "P3") (pin "MP1") (pinfunction "MP1_MP1") (pintype "passive"))
    )
    (net (code "59") (name "unconnected-(P3-PadMP2)") (class "Default")
      (node (ref "P3") (pin "MP2") (pinfunction "MP2_MP2") (pintype "passive"))
    )
    (net (code "60") (name "unconnected-(P4-PadMP1)") (class "Default")
      (node (ref "P4") (pin "MP1") (pinfunction "MP1_MP1") (pintype "passive"))
    )
    (net (code "61") (name "unconnected-(P4-PadMP2)") (class "Default")
      (node (ref "P4") (pin "MP2") (pinfunction "MP2_MP2") (pintype "passive"))
    )
    (net (code "62") (name "unconnected-(R27-Pad1)") (class "Default")
      (node (ref "R27") (pin "1") (pinfunction "1_1") (pintype "passive"))
    )
    (net (code "63") (name "unconnected-(R53-Pad1)") (class "Default")
      (node (ref "R53") (pin "1") (pinfunction "1_1") (pintype "passive"))
    )
  )
)
